# clock.net
KiCad netlist of a schematic drawn in Altium Designer
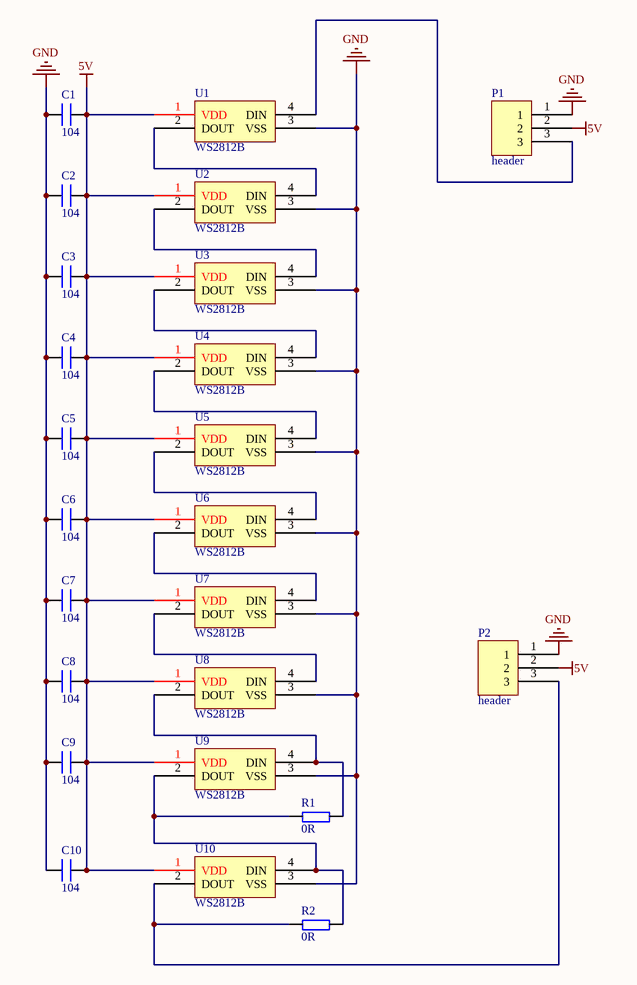
[diagram p0: clock.SchDoc]

(export (version "E")
  (design (tool "Eeschema 10.0.6"))
  (components
    (comp (ref "C1") (value "104") (footprint "0603P") (libsource (lib "Explorer STM32F407封装库") (part "C")))
    (comp (ref "C2") (value "104") (footprint "0603P") (libsource (lib "Explorer STM32F407封装库") (part "C")))
    (comp (ref "C3") (value "104") (footprint "0603P") (libsource (lib "Explorer STM32F407封装库") (part "C")))
    (comp (ref "C4") (value "104") (footprint "0603P") (libsource (lib "Explorer STM32F407封装库") (part "C")))
    (comp (ref "C5") (value "104") (footprint "0603P") (libsource (lib "Explorer STM32F407封装库") (part "C")))
    (comp (ref "C6") (value "104") (footprint "0603P") (libsource (lib "Explorer STM32F407封装库") (part "C")))
    (comp (ref "C7") (value "104") (footprint "0603P") (libsource (lib "Explorer STM32F407封装库") (part "C")))
    (comp (ref "C8") (value "104") (footprint "0603P") (libsource (lib "Explorer STM32F407封装库") (part "C")))
    (comp (ref "C9") (value "104") (footprint "0603P") (libsource (lib "Explorer STM32F407封装库") (part "C")))
    (comp (ref "C10") (value "104") (footprint "0603P") (libsource (lib "Explorer STM32F407封装库") (part "C")))
    (comp (ref "P1") (value "header") (footprint "HEADWR3-1") (libsource (lib "clock") (part "header3")))
    (comp (ref "P2") (value "header") (footprint "HEADWR3-1") (libsource (lib "clock") (part "header3")))
    (comp (ref "R1") (value "0R") (footprint "0603P") (libsource (lib "Explorer STM32F407封装库") (part "R")))
    (comp (ref "R2") (value "0R") (footprint "0603P") (libsource (lib "Explorer STM32F407封装库") (part "R")))
    (comp (ref "U1") (value "WS2812B") (footprint "ws2812b") (libsource (lib "clock") (part "WS2812B")))
    (comp (ref "U2") (value "WS2812B") (footprint "ws2812b") (libsource (lib "clock") (part "WS2812B")))
    (comp (ref "U3") (value "WS2812B") (footprint "ws2812b") (libsource (lib "clock") (part "WS2812B")))
    (comp (ref "U4") (value "WS2812B") (footprint "ws2812b") (libsource (lib "clock") (part "WS2812B")))
    (comp (ref "U5") (value "WS2812B") (footprint "ws2812b") (libsource (lib "clock") (part "WS2812B")))
    (comp (ref "U6") (value "WS2812B") (footprint "ws2812b") (libsource (lib "clock") (part "WS2812B")))
    (comp (ref "U7") (value "WS2812B") (footprint "ws2812b") (libsource (lib "clock") (part "WS2812B")))
    (comp (ref "U8") (value "WS2812B") (footprint "ws2812b") (libsource (lib "clock") (part "WS2812B")))
    (comp (ref "U9") (value "WS2812B") (footprint "ws2812b") (libsource (lib "clock") (part "WS2812B")))
    (comp (ref "U10") (value "WS2812B") (footprint "ws2812b") (libsource (lib "clock") (part "WS2812B")))
  )
  (nets
    (net (code "1") (name "5V") (class "Default")
      (node (ref "C1") (pin "2") (pintype "passive"))
      (node (ref "C10") (pin "2") (pintype "passive"))
      (node (ref "C2") (pin "2") (pintype "passive"))
      (node (ref "C3") (pin "2") (pintype "passive"))
      (node (ref "C4") (pin "2") (pintype "passive"))
      (node (ref "C5") (pin "2") (pintype "passive"))
      (node (ref "C6") (pin "2") (pintype "passive"))
      (node (ref "C7") (pin "2") (pintype "passive"))
      (node (ref "C8") (pin "2") (pintype "passive"))
      (node (ref "C9") (pin "2") (pintype "passive"))
      (node (ref "P1") (pin "2") (pinfunction "2_2") (pintype "passive"))
      (node (ref "P2") (pin "2") (pinfunction "2_2") (pintype "passive"))
      (node (ref "U1") (pin "1") (pinfunction "VDD_1") (pintype "passive"))
      (node (ref "U10") (pin "1") (pinfunction "VDD_1") (pintype "passive"))
      (node (ref "U2") (pin "1") (pinfunction "VDD_1") (pintype "passive"))
      (node (ref "U3") (pin "1") (pinfunction "VDD_1") (pintype "passive"))
      (node (ref "U4") (pin "1") (pinfunction "VDD_1") (pintype "passive"))
      (node (ref "U5") (pin "1") (pinfunction "VDD_1") (pintype "passive"))
      (node (ref "U6") (pin "1") (pinfunction "VDD_1") (pintype "passive"))
      (node (ref "U7") (pin "1") (pinfunction "VDD_1") (pintype "passive"))
      (node (ref "U8") (pin "1") (pinfunction "VDD_1") (pintype "passive"))
      (node (ref "U9") (pin "1") (pinfunction "VDD_1") (pintype "passive"))
    )
    (net (code "2") (name "GND") (class "Default")
      (node (ref "C1") (pin "1") (pintype "passive"))
      (node (ref "C10") (pin "1") (pintype "passive"))
      (node (ref "C2") (pin "1") (pintype "passive"))
      (node (ref "C3") (pin "1") (pintype "passive"))
      (node (ref "C4") (pin "1") (pintype "passive"))
      (node (ref "C5") (pin "1") (pintype "passive"))
      (node (ref "C6") (pin "1") (pintype "passive"))
      (node (ref "C7") (pin "1") (pintype "passive"))
      (node (ref "C8") (pin "1") (pintype "passive"))
      (node (ref "C9") (pin "1") (pintype "passive"))
      (node (ref "P1") (pin "1") (pinfunction "1_1") (pintype "passive"))
      (node (ref "P2") (pin "1") (pinfunction "1_1") (pintype "passive"))
      (node (ref "U1") (pin "3") (pinfunction "VSS_3") (pintype "passive"))
      (node (ref "U10") (pin "3") (pinfunction "VSS_3") (pintype "passive"))
      (node (ref "U2") (pin "3") (pinfunction "VSS_3") (pintype "passive"))
      (node (ref "U3") (pin "3") (pinfunction "VSS_3") (pintype "passive"))
      (node (ref "U4") (pin "3") (pinfunction "VSS_3") (pintype "passive"))
      (node (ref "U5") (pin "3") (pinfunction "VSS_3") (pintype "passive"))
      (node (ref "U6") (pin "3") (pinfunction "VSS_3") (pintype "passive"))
      (node (ref "U7") (pin "3") (pinfunction "VSS_3") (pintype "passive"))
      (node (ref "U8") (pin "3") (pinfunction "VSS_3") (pintype "passive"))
      (node (ref "U9") (pin "3") (pinfunction "VSS_3") (pintype "passive"))
    )
    (net (code "3") (name "Net-(U1-DIN)") (class "Default")
      (node (ref "P1") (pin "3") (pinfunction "3_3") (pintype "passive"))
      (node (ref "U1") (pin "4") (pinfunction "DIN_4") (pintype "passive"))
    )
    (net (code "4") (name "Net-(U1-DOUT)") (class "Default")
      (node (ref "U1") (pin "2") (pinfunction "DOUT_2") (pintype "passive"))
      (node (ref "U2") (pin "4") (pinfunction "DIN_4") (pintype "passive"))
    )
    (net (code "5") (name "Net-(U2-DOUT)") (class "Default")
      (node (ref "U2") (pin "2") (pinfunction "DOUT_2") (pintype "passive"))
      (node (ref "U3") (pin "4") (pinfunction "DIN_4") (pintype "passive"))
    )
    (net (code "6") (name "Net-(U3-DOUT)") (class "Default")
      (node (ref "U3") (pin "2") (pinfunction "DOUT_2") (pintype "passive"))
      (node (ref "U4") (pin "4") (pinfunction "DIN_4") (pintype "passive"))
    )
    (net (code "7") (name "Net-(U4-DOUT)") (class "Default")
      (node (ref "U4") (pin "2") (pinfunction "DOUT_2") (pintype "passive"))
      (node (ref "U5") (pin "4") (pinfunction "DIN_4") (pintype "passive"))
    )
    (net (code "8") (name "Net-(U5-DOUT)") (class "Default")
      (node (ref "U5") (pin "2") (pinfunction "DOUT_2") (pintype "passive"))
      (node (ref "U6") (pin "4") (pinfunction "DIN_4") (pintype "passive"))
    )
    (net (code "9") (name "Net-(U6-DOUT)") (class "Default")
      (node (ref "U6") (pin "2") (pinfunction "DOUT_2") (pintype "passive"))
      (node (ref "U7") (pin "4") (pinfunction "DIN_4") (pintype "passive"))
    )
    (net (code "10") (name "Net-(U7-DOUT)") (class "Default")
      (node (ref "U7") (pin "2") (pinfunction "DOUT_2") (pintype "passive"))
      (node (ref "U8") (pin "4") (pinfunction "DIN_4") (pintype "passive"))
    )
    (net (code "11") (name "Net-(U8-DOUT)") (class "Default")
      (node (ref "R1") (pin "2") (pintype "passive"))
      (node (ref "U8") (pin "2") (pinfunction "DOUT_2") (pintype "passive"))
      (node (ref "U9") (pin "4") (pinfunction "DIN_4") (pintype "passive"))
    )
    (net (code "12") (name "Net-(U10-DIN)") (class "Default")
      (node (ref "R1") (pin "1") (pintype "passive"))
      (node (ref "R2") (pin "2") (pintype "passive"))
      (node (ref "U10") (pin "4") (pinfunction "DIN_4") (pintype "passive"))
      (node (ref "U9") (pin "2") (pinfunction "DOUT_2") (pintype "passive"))
    )
    (net (code "13") (name "Net-(U10-DOUT)") (class "Default")
      (node (ref "P2") (pin "3") (pinfunction "3_3") (pintype "passive"))
      (node (ref "R2") (pin "1") (pintype "passive"))
      (node (ref "U10") (pin "2") (pinfunction "DOUT_2") (pintype "passive"))
    )
  )
)
